# GateDriverPowerSupply.net
KiCad netlist of a schematic drawn in Altium Designer
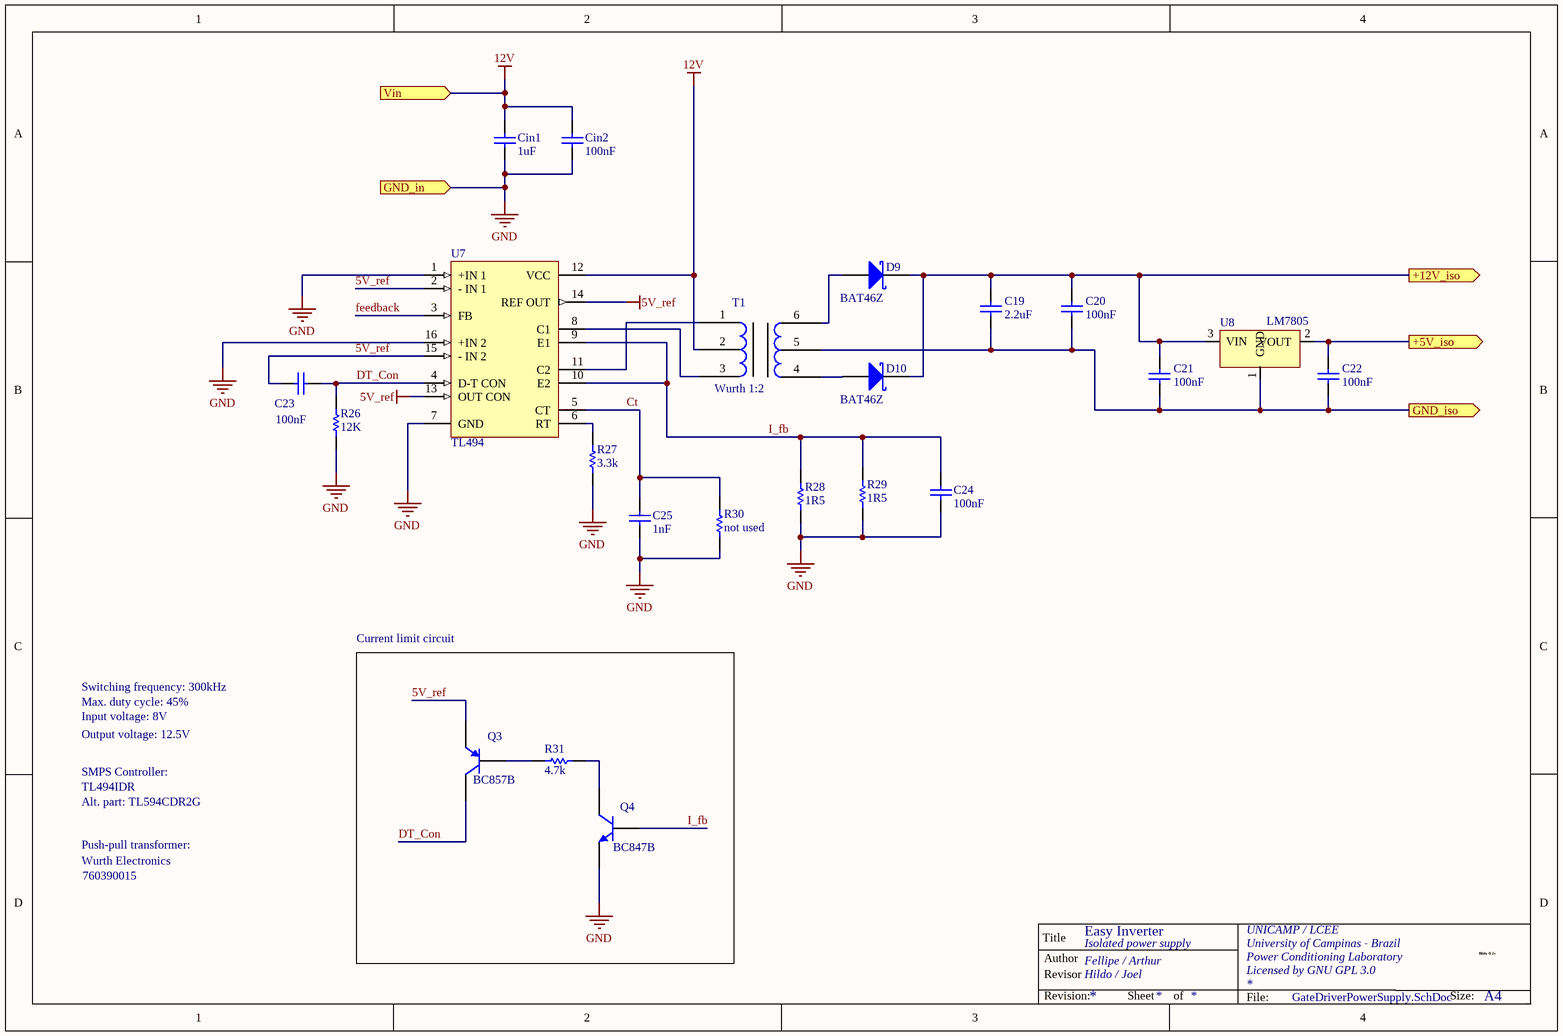
[diagram p0: GateDriverPowerSupply.SchDoc]

(export (version "E")
  (design (tool "Eeschema 10.0.6"))
  (components
    (comp (ref "C19")
      (value "2.2uF")
      (footprint "0805_W")
      (description "Capacitor nao polarizado")
      (libsource (lib "Sch_LCEE") (part "Capacitor_nao_polarizado"))
    )
    (comp (ref "C20")
      (value "100nF")
      (footprint "0805_W")
      (description "Capacitor nao polarizado")
      (libsource (lib "Sch_LCEE") (part "Capacitor_nao_polarizado"))
    )
    (comp (ref "C21")
      (value "100nF")
      (footprint "0805_W")
      (description "Capacitor nao polarizado")
      (libsource (lib "Sch_LCEE") (part "Capacitor_nao_polarizado"))
    )
    (comp (ref "C22")
      (value "100nF")
      (footprint "0805_W")
      (description "Capacitor nao polarizado")
      (libsource (lib "Sch_LCEE") (part "Capacitor_nao_polarizado"))
    )
    (comp (ref "C23")
      (value "100nF")
      (footprint "0805_W")
      (description "Capacitor")
      (libsource (lib "Inversor_LCEE") (part "Cap_0805"))
    )
    (comp (ref "C24")
      (value "100nF")
      (footprint "0805_W")
      (description "Capacitor")
      (libsource (lib "Inversor_LCEE") (part "Cap_0805"))
    )
    (comp (ref "C25")
      (value "1nF")
      (footprint "0805_W")
      (description "Capacitor")
      (libsource (lib "Inversor_LCEE") (part "Cap_0805"))
    )
    (comp (ref "Cin1")
      (value "1uF")
      (footprint "0805_W")
      (description "Capacitor")
      (libsource (lib "Inversor_LCEE") (part "Cap_0805"))
    )
    (comp (ref "Cin2")
      (value "100nF")
      (footprint "0805_W")
      (description "Capacitor")
      (libsource (lib "Inversor_LCEE") (part "Cap_0805"))
    )
    (comp (ref "D9")
      (value "BAT46Z")
      (footprint "SOD-123")
      (description "Schottky Diode")
      (libsource (lib "Miscellaneous Devices") (part "D Schottky"))
    )
    (comp (ref "D10")
      (value "BAT46Z")
      (footprint "SOD-123")
      (description "Schottky Diode")
      (libsource (lib "Miscellaneous Devices") (part "D Schottky"))
    )
    (comp (ref "Q3")
      (value "BC857B")
      (footprint "SOT-23-TT3_N")
      (description "PNP General-purpose Transistor")
      (libsource (lib "Philips Discrete BJT - Low Power") (part "BC857"))
    )
    (comp (ref "Q4")
      (value "BC847B")
      (footprint "SOT-23-TT3_N")
      (description "NPN General-purpose Transistor")
      (libsource (lib "Philips Discrete BJT - Low Power") (part "BC847"))
    )
    (comp (ref "R26")
      (value "12K")
      (footprint "0805_W")
      (description "Resistor")
      (libsource (lib "Inversor_LCEE") (part "Res_0805"))
    )
    (comp (ref "R27")
      (value "3.3k")
      (footprint "0805_W")
      (description "Resistor")
      (libsource (lib "Inversor_LCEE") (part "Res_0805"))
    )
    (comp (ref "R28")
      (value "1R5")
      (footprint "0805_W")
      (description "Resistor")
      (libsource (lib "Inversor_LCEE") (part "Res_0805"))
    )
    (comp (ref "R29")
      (value "1R5")
      (footprint "0805_W")
      (description "Resistor")
      (libsource (lib "Inversor_LCEE") (part "Res_0805"))
    )
    (comp (ref "R30")
      (value "not used")
      (footprint "0805_W")
      (description "Resistor")
      (fields
        (field (name "MANUFACTURER") "Generic Components")
        (field (name "PUBLISHER") "Altium Hobart Technology Centre")
      )
      (libsource (lib "Inversor_LCEE") (part "Res_0805"))
    )
    (comp (ref "R31")
      (value "4.7k")
      (footprint "0805_W")
      (description "Resistor")
      (libsource (lib "Inversor_LCEE") (part "Res_0805"))
    )
    (comp (ref "T1") (value "Wurth 1:2") (footprint "Trafo") (libsource (lib "Sch_LCEE") (part "Trafo-TI")))
    (comp (ref "U7")
      (value "TL494")
      (footprint "SOIC16_M")
      (description "Pulse-Width-Modulation Control Circuit")
      (libsource (lib "TI Power Mgt Power Controller") (part "TL494ID"))
    )
    (comp (ref "U8") (value "LM7805") (footprint "LM78XX") (libsource (lib "Sch_LCEE") (part "LM7805")))
  )
  (nets
    (net (code "1") (name "/+5V_iso") (class "Default")
      (node (ref "C22") (pin "1") (pinfunction "1_1") (pintype "passive"))
      (node (ref "U8") (pin "2") (pinfunction "VOUT_2") (pintype "passive"))
    )
    (net (code "2") (name "/+12V_iso") (class "Default")
      (node (ref "C19") (pin "1") (pinfunction "1_1") (pintype "passive"))
      (node (ref "C20") (pin "1") (pinfunction "1_1") (pintype "passive"))
      (node (ref "C21") (pin "1") (pinfunction "1_1") (pintype "passive"))
      (node (ref "D10") (pin "2") (pinfunction "K_2") (pintype "passive"))
      (node (ref "D9") (pin "2") (pinfunction "K_2") (pintype "passive"))
      (node (ref "U8") (pin "3") (pinfunction "VIN_3") (pintype "passive"))
    )
    (net (code "3") (name "/Ct") (class "Default")
      (node (ref "C25") (pin "1") (pinfunction "1_1") (pintype "passive"))
      (node (ref "R30") (pin "2") (pinfunction "2_2") (pintype "passive"))
      (node (ref "U7") (pin "5") (pinfunction "CT_5") (pintype "passive"))
    )
    (net (code "4") (name "/DT_Con") (class "Default")
      (node (ref "C23") (pin "2") (pinfunction "2_2") (pintype "passive"))
      (node (ref "Q3") (pin "3") (pinfunction "C_3") (pintype "passive"))
      (node (ref "R26") (pin "2") (pinfunction "2_2") (pintype "passive"))
      (node (ref "U7") (pin "4") (pinfunction "D-T_CON_4") (pintype "input"))
    )
    (net (code "5") (name "/GND_iso") (class "Default")
      (node (ref "C19") (pin "2") (pinfunction "2_2") (pintype "passive"))
      (node (ref "C20") (pin "2") (pinfunction "2_2") (pintype "passive"))
      (node (ref "C21") (pin "2") (pinfunction "2_2") (pintype "passive"))
      (node (ref "C22") (pin "2") (pinfunction "2_2") (pintype "passive"))
      (node (ref "T1") (pin "5") (pinfunction "5_5") (pintype "passive"))
      (node (ref "U8") (pin "1") (pinfunction "GND_1") (pintype "passive"))
    )
    (net (code "6") (name "/I_fb") (class "Default")
      (node (ref "C24") (pin "2") (pinfunction "2_2") (pintype "passive"))
      (node (ref "Q4") (pin "1") (pinfunction "B_1") (pintype "passive"))
      (node (ref "R28") (pin "2") (pinfunction "2_2") (pintype "passive"))
      (node (ref "R29") (pin "2") (pinfunction "2_2") (pintype "passive"))
      (node (ref "U7") (pin "10") (pinfunction "E2_10") (pintype "passive"))
      (node (ref "U7") (pin "9") (pinfunction "E1_9") (pintype "passive"))
    )
    (net (code "7") (name "/feedback") (class "Default")
      (node (ref "U7") (pin "3") (pinfunction "FB_3") (pintype "input"))
    )
    (net (code "8") (name "5V_ref") (class "Default")
      (node (ref "C23") (pin "1") (pinfunction "1_1") (pintype "passive"))
      (node (ref "Q3") (pin "2") (pinfunction "E_2") (pintype "passive"))
      (node (ref "U7") (pin "13") (pinfunction "OUT_CON_13") (pintype "input"))
      (node (ref "U7") (pin "14") (pinfunction "REF_OUT_14") (pintype "output"))
      (node (ref "U7") (pin "15") (pinfunction "-_IN_2_15") (pintype "input"))
      (node (ref "U7") (pin "2") (pinfunction "-_IN_1_2") (pintype "input"))
    )
    (net (code "9") (name "12V") (class "Default")
      (node (ref "Cin1") (pin "1") (pinfunction "1_1") (pintype "passive"))
      (node (ref "Cin2") (pin "1") (pinfunction "1_1") (pintype "passive"))
      (node (ref "T1") (pin "2") (pinfunction "2_2") (pintype "passive"))
      (node (ref "U7") (pin "12") (pinfunction "VCC_12") (pintype "power_in"))
    )
    (net (code "10") (name "GND") (class "Default")
      (node (ref "C24") (pin "1") (pinfunction "1_1") (pintype "passive"))
      (node (ref "C25") (pin "2") (pinfunction "2_2") (pintype "passive"))
      (node (ref "Cin1") (pin "2") (pinfunction "2_2") (pintype "passive"))
      (node (ref "Cin2") (pin "2") (pinfunction "2_2") (pintype "passive"))
      (node (ref "Q4") (pin "2") (pinfunction "E_2") (pintype "passive"))
      (node (ref "R26") (pin "1") (pinfunction "1_1") (pintype "passive"))
      (node (ref "R27") (pin "1") (pinfunction "1_1") (pintype "passive"))
      (node (ref "R28") (pin "1") (pinfunction "1_1") (pintype "passive"))
      (node (ref "R29") (pin "1") (pinfunction "1_1") (pintype "passive"))
      (node (ref "R30") (pin "1") (pinfunction "1_1") (pintype "passive"))
      (node (ref "U7") (pin "1") (pinfunction "+IN_1_1") (pintype "input"))
      (node (ref "U7") (pin "16") (pinfunction "+IN_2_16") (pintype "input"))
      (node (ref "U7") (pin "7") (pinfunction "GND_7") (pintype "power_in"))
    )
    (net (code "11") (name "Net-(D9-A)") (class "Default")
      (node (ref "D9") (pin "1") (pinfunction "A_1") (pintype "passive"))
      (node (ref "T1") (pin "6") (pinfunction "6_6") (pintype "passive"))
    )
    (net (code "12") (name "Net-(D10-A)") (class "Default")
      (node (ref "D10") (pin "1") (pinfunction "A_1") (pintype "passive"))
      (node (ref "T1") (pin "4") (pinfunction "4_4") (pintype "passive"))
    )
    (net (code "13") (name "Net-(Q3-B)") (class "Default")
      (node (ref "Q3") (pin "1") (pinfunction "B_1") (pintype "passive"))
      (node (ref "R31") (pin "2") (pinfunction "2_2") (pintype "passive"))
    )
    (net (code "14") (name "Net-(Q4-C)") (class "Default")
      (node (ref "Q4") (pin "3") (pinfunction "C_3") (pintype "passive"))
      (node (ref "R31") (pin "1") (pinfunction "1_1") (pintype "passive"))
    )
    (net (code "15") (name "Net-(U7-C1)") (class "Default")
      (node (ref "T1") (pin "3") (pinfunction "3_3") (pintype "passive"))
      (node (ref "U7") (pin "8") (pinfunction "C1_8") (pintype "passive"))
    )
    (net (code "16") (name "Net-(U7-C2)") (class "Default")
      (node (ref "T1") (pin "1") (pinfunction "1_1") (pintype "passive"))
      (node (ref "U7") (pin "11") (pinfunction "C2_11") (pintype "passive"))
    )
    (net (code "17") (name "Net-(U7-RT)") (class "Default")
      (node (ref "R27") (pin "2") (pinfunction "2_2") (pintype "passive"))
      (node (ref "U7") (pin "6") (pinfunction "RT_6") (pintype "passive"))
    )
  )
)
